# WiiIr.net
KiCad netlist of a schematic drawn in EAGLE
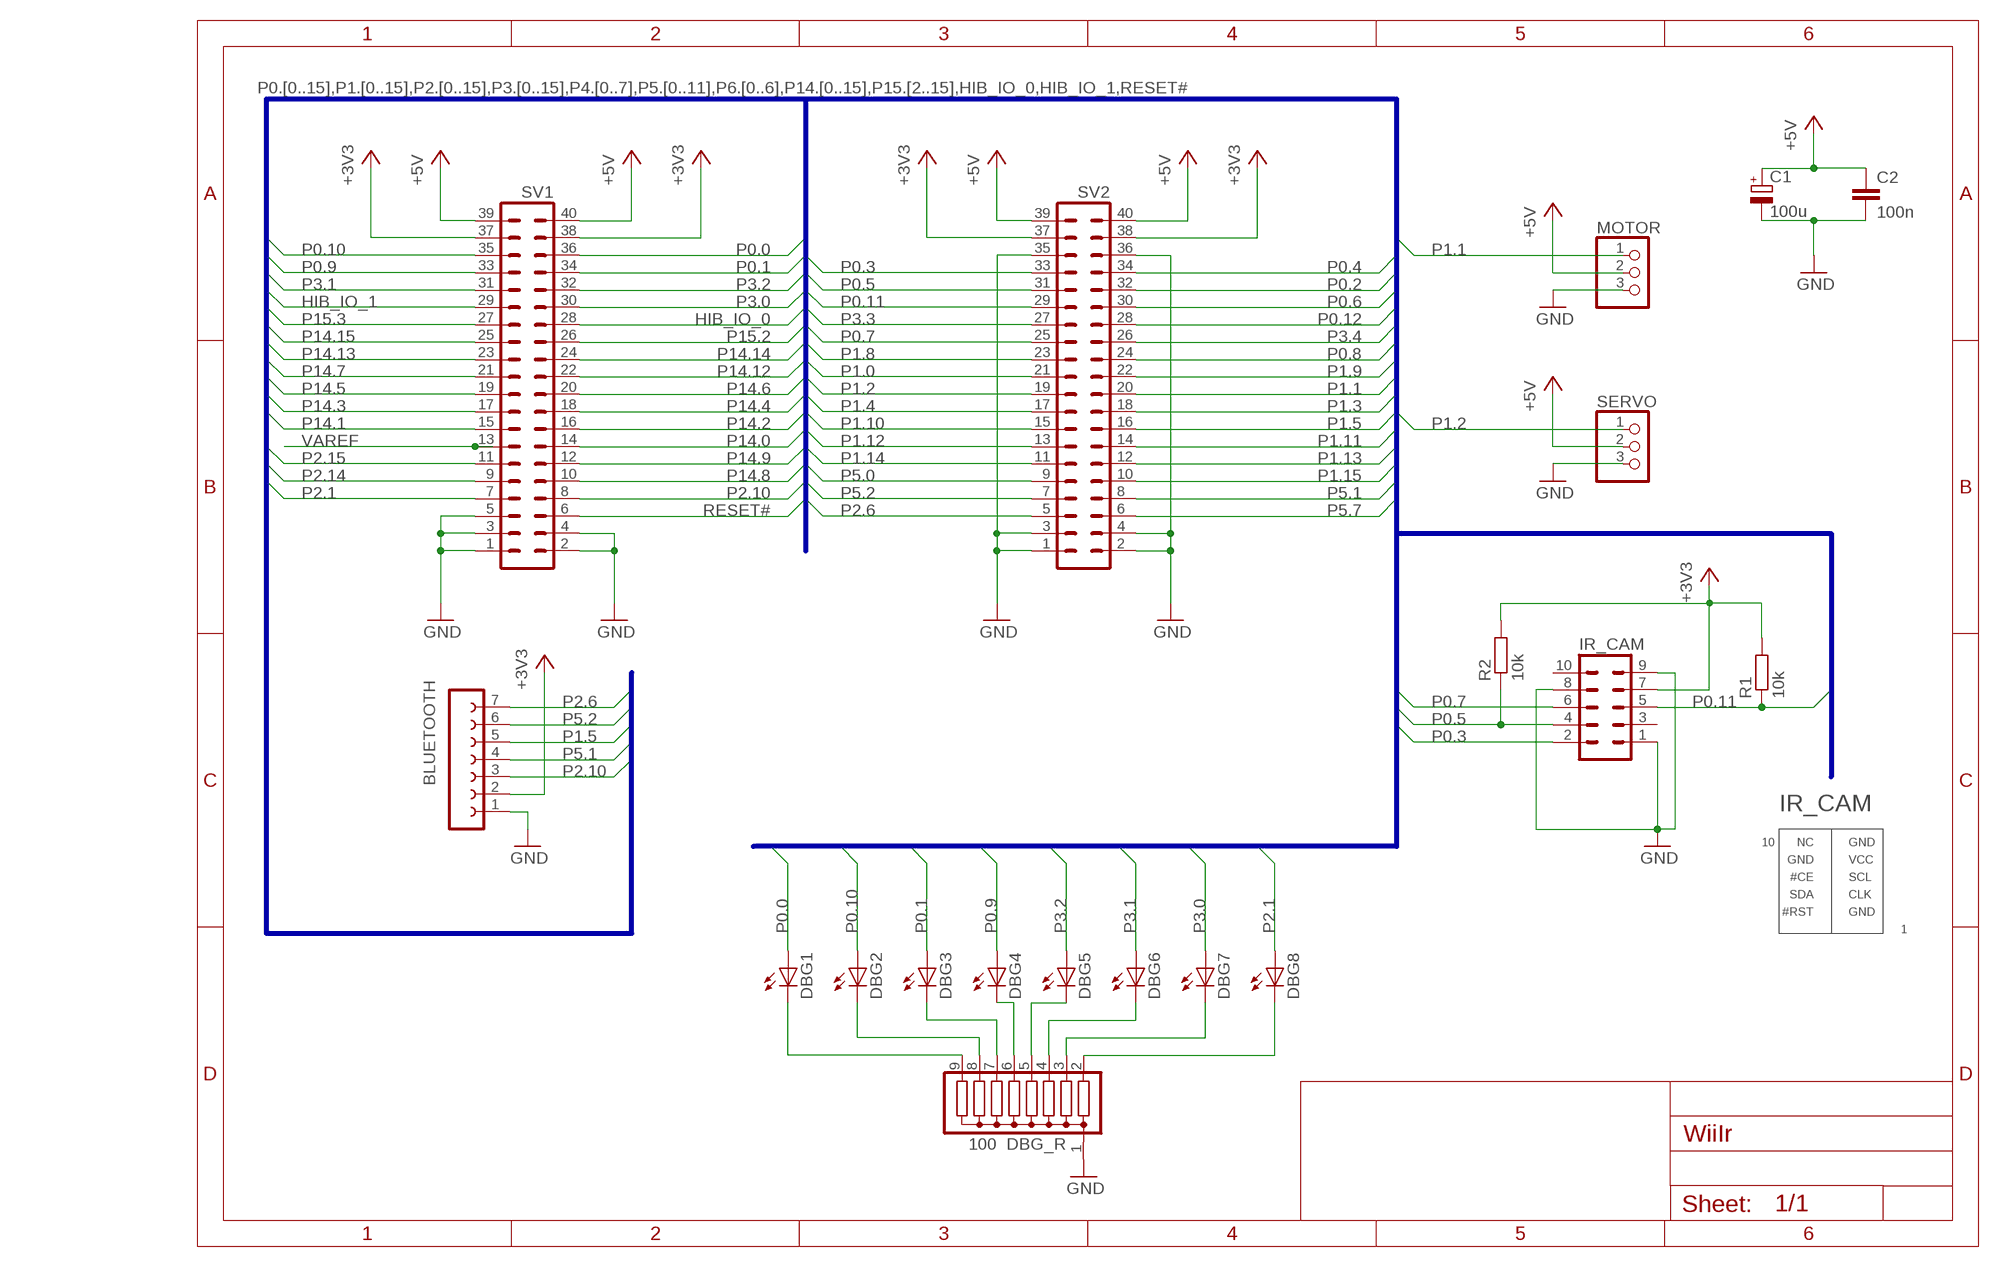
[diagram p0: schematic, sheet 1]

(export (version "E")
  (design (tool "Eeschema 10.0.6"))
  (components
    (comp (ref "BLUETOOTH")
      (value "FE07-1")
      (footprint "eagle-import:FE07")
      (libsource (lib "eagle-import") (part "FE07-1"))
    )
    (comp (ref "C1")
      (value "100u")
      (footprint "eagle-import:E2,5-7")
      (libsource (lib "eagle-import") (part "CPOL-EUE2.5-7"))
    )
    (comp (ref "C2")
      (value "100n")
      (footprint "eagle-import:C025-025X050")
      (libsource (lib "eagle-import") (part "C-EU025-025X050"))
    )
    (comp (ref "DBG1")
      (value "LEDSQR2X5")
      (footprint "eagle-import:LED2X5")
      (libsource (lib "eagle-import") (part "LEDSQR2X5"))
    )
    (comp (ref "DBG2")
      (value "LEDSQR2X5")
      (footprint "eagle-import:LED2X5")
      (libsource (lib "eagle-import") (part "LEDSQR2X5"))
    )
    (comp (ref "DBG3")
      (value "LEDSQR2X5")
      (footprint "eagle-import:LED2X5")
      (libsource (lib "eagle-import") (part "LEDSQR2X5"))
    )
    (comp (ref "DBG4")
      (value "LEDSQR2X5")
      (footprint "eagle-import:LED2X5")
      (libsource (lib "eagle-import") (part "LEDSQR2X5"))
    )
    (comp (ref "DBG5")
      (value "LEDSQR2X5")
      (footprint "eagle-import:LED2X5")
      (libsource (lib "eagle-import") (part "LEDSQR2X5"))
    )
    (comp (ref "DBG6")
      (value "LEDSQR2X5")
      (footprint "eagle-import:LED2X5")
      (libsource (lib "eagle-import") (part "LEDSQR2X5"))
    )
    (comp (ref "DBG7")
      (value "LEDSQR2X5")
      (footprint "eagle-import:LED2X5")
      (libsource (lib "eagle-import") (part "LEDSQR2X5"))
    )
    (comp (ref "DBG8")
      (value "LEDSQR2X5")
      (footprint "eagle-import:LED2X5")
      (libsource (lib "eagle-import") (part "LEDSQR2X5"))
    )
    (comp (ref "DBG_R")
      (value "100")
      (footprint "eagle-import:SIL9")
      (libsource (lib "eagle-import") (part "G08R"))
    )
    (comp (ref "IR_CAM")
      (value "ML10")
      (footprint "eagle-import:ML10")
      (libsource (lib "eagle-import") (part "ML10"))
    )
    (comp (ref "MOTOR")
      (value "PINHD-1X3/90")
      (footprint "eagle-import:1X03_90")
      (libsource (lib "eagle-import") (part "PINHD-1X3/90"))
    )
    (comp (ref "R1")
      (value "10k")
      (footprint "eagle-import:0207_12")
      (libsource (lib "eagle-import") (part "R-EU_0207/12"))
    )
    (comp (ref "R2")
      (value "10k")
      (footprint "eagle-import:0207_10")
      (libsource (lib "eagle-import") (part "R-EU_0207/10"))
    )
    (comp (ref "SERVO")
      (value "PINHD-1X3/90")
      (footprint "eagle-import:1X03_90")
      (libsource (lib "eagle-import") (part "PINHD-1X3/90"))
    )
    (comp (ref "SV1")
      (value "MA20-2")
      (footprint "eagle-import:MA20-2")
      (libsource (lib "eagle-import") (part "MA20-2"))
    )
    (comp (ref "SV2")
      (value "MA20-2")
      (footprint "eagle-import:MA20-2")
      (libsource (lib "eagle-import") (part "MA20-2"))
    )
  )
  (nets
    (net (code "1") (name "+3V3") (class "Default")
      (node (ref "BLUETOOTH") (pin "2") (pinfunction "2_2") (pintype "passive"))
      (node (ref "IR_CAM") (pin "7") (pinfunction "7_7") (pintype "passive"))
      (node (ref "R1") (pin "2") (pinfunction "2_2") (pintype "passive"))
      (node (ref "R2") (pin "2") (pinfunction "2_2") (pintype "passive"))
      (node (ref "SV1") (pin "37") (pinfunction "37_37") (pintype "passive"))
      (node (ref "SV1") (pin "38") (pinfunction "38_38") (pintype "passive"))
      (node (ref "SV2") (pin "37") (pinfunction "37_37") (pintype "passive"))
      (node (ref "SV2") (pin "38") (pinfunction "38_38") (pintype "passive"))
    )
    (net (code "2") (name "+5V") (class "Default")
      (node (ref "C1") (pin "+") (pinfunction "+_+") (pintype "passive"))
      (node (ref "C2") (pin "1") (pinfunction "1_1") (pintype "passive"))
      (node (ref "MOTOR") (pin "2") (pinfunction "2_2") (pintype "passive"))
      (node (ref "SERVO") (pin "2") (pinfunction "2_2") (pintype "passive"))
      (node (ref "SV1") (pin "39") (pinfunction "39_39") (pintype "passive"))
      (node (ref "SV1") (pin "40") (pinfunction "40_40") (pintype "passive"))
      (node (ref "SV2") (pin "39") (pinfunction "39_39") (pintype "passive"))
      (node (ref "SV2") (pin "40") (pinfunction "40_40") (pintype "passive"))
    )
    (net (code "3") (name "/HIB_IO_0") (class "Default")
      (node (ref "SV1") (pin "28") (pinfunction "28_28") (pintype "passive"))
    )
    (net (code "4") (name "/HIB_IO_1") (class "Default")
      (node (ref "SV1") (pin "29") (pinfunction "29_29") (pintype "passive"))
    )
    (net (code "5") (name "/P0.0") (class "Default")
      (node (ref "DBG1") (pin "A") (pinfunction "A_A") (pintype "passive"))
      (node (ref "SV1") (pin "36") (pinfunction "36_36") (pintype "passive"))
    )
    (net (code "6") (name "/P0.1") (class "Default")
      (node (ref "DBG3") (pin "A") (pinfunction "A_A") (pintype "passive"))
      (node (ref "SV1") (pin "34") (pinfunction "34_34") (pintype "passive"))
    )
    (net (code "7") (name "/P0.2") (class "Default")
      (node (ref "SV2") (pin "32") (pinfunction "32_32") (pintype "passive"))
    )
    (net (code "8") (name "/P0.3") (class "Default")
      (node (ref "IR_CAM") (pin "2") (pinfunction "2_2") (pintype "passive"))
      (node (ref "SV2") (pin "33") (pinfunction "33_33") (pintype "passive"))
    )
    (net (code "9") (name "/P0.4") (class "Default")
      (node (ref "SV2") (pin "34") (pinfunction "34_34") (pintype "passive"))
    )
    (net (code "10") (name "/P0.5") (class "Default")
      (node (ref "IR_CAM") (pin "4") (pinfunction "4_4") (pintype "passive"))
      (node (ref "R2") (pin "1") (pinfunction "1_1") (pintype "passive"))
      (node (ref "SV2") (pin "31") (pinfunction "31_31") (pintype "passive"))
    )
    (net (code "11") (name "/P0.6") (class "Default")
      (node (ref "SV2") (pin "30") (pinfunction "30_30") (pintype "passive"))
    )
    (net (code "12") (name "/P0.7") (class "Default")
      (node (ref "IR_CAM") (pin "6") (pinfunction "6_6") (pintype "passive"))
      (node (ref "SV2") (pin "25") (pinfunction "25_25") (pintype "passive"))
    )
    (net (code "13") (name "/P0.8") (class "Default")
      (node (ref "SV2") (pin "24") (pinfunction "24_24") (pintype "passive"))
    )
    (net (code "14") (name "/P0.9") (class "Default")
      (node (ref "DBG4") (pin "A") (pinfunction "A_A") (pintype "passive"))
      (node (ref "SV1") (pin "33") (pinfunction "33_33") (pintype "passive"))
    )
    (net (code "15") (name "/P0.10") (class "Default")
      (node (ref "DBG2") (pin "A") (pinfunction "A_A") (pintype "passive"))
      (node (ref "SV1") (pin "35") (pinfunction "35_35") (pintype "passive"))
    )
    (net (code "16") (name "/P0.11") (class "Default")
      (node (ref "IR_CAM") (pin "5") (pinfunction "5_5") (pintype "passive"))
      (node (ref "R1") (pin "1") (pinfunction "1_1") (pintype "passive"))
      (node (ref "SV2") (pin "29") (pinfunction "29_29") (pintype "passive"))
    )
    (net (code "17") (name "/P0.12") (class "Default")
      (node (ref "SV2") (pin "28") (pinfunction "28_28") (pintype "passive"))
    )
    (net (code "18") (name "/P1.0") (class "Default")
      (node (ref "SV2") (pin "21") (pinfunction "21_21") (pintype "passive"))
    )
    (net (code "19") (name "/P1.1") (class "Default")
      (node (ref "MOTOR") (pin "1") (pinfunction "1_1") (pintype "passive"))
      (node (ref "SV2") (pin "20") (pinfunction "20_20") (pintype "passive"))
    )
    (net (code "20") (name "/P1.2") (class "Default")
      (node (ref "SERVO") (pin "1") (pinfunction "1_1") (pintype "passive"))
      (node (ref "SV2") (pin "19") (pinfunction "19_19") (pintype "passive"))
    )
    (net (code "21") (name "/P1.3") (class "Default")
      (node (ref "SV2") (pin "18") (pinfunction "18_18") (pintype "passive"))
    )
    (net (code "22") (name "/P1.4") (class "Default")
      (node (ref "SV2") (pin "17") (pinfunction "17_17") (pintype "passive"))
    )
    (net (code "23") (name "/P1.5") (class "Default")
      (node (ref "BLUETOOTH") (pin "5") (pinfunction "5_5") (pintype "passive"))
      (node (ref "SV2") (pin "16") (pinfunction "16_16") (pintype "passive"))
    )
    (net (code "24") (name "/P1.8") (class "Default")
      (node (ref "SV2") (pin "23") (pinfunction "23_23") (pintype "passive"))
    )
    (net (code "25") (name "/P1.9") (class "Default")
      (node (ref "SV2") (pin "22") (pinfunction "22_22") (pintype "passive"))
    )
    (net (code "26") (name "/P1.10") (class "Default")
      (node (ref "SV2") (pin "15") (pinfunction "15_15") (pintype "passive"))
    )
    (net (code "27") (name "/P1.11") (class "Default")
      (node (ref "SV2") (pin "14") (pinfunction "14_14") (pintype "passive"))
    )
    (net (code "28") (name "/P1.12") (class "Default")
      (node (ref "SV2") (pin "13") (pinfunction "13_13") (pintype "passive"))
    )
    (net (code "29") (name "/P1.13") (class "Default")
      (node (ref "SV2") (pin "12") (pinfunction "12_12") (pintype "passive"))
    )
    (net (code "30") (name "/P1.14") (class "Default")
      (node (ref "SV2") (pin "11") (pinfunction "11_11") (pintype "passive"))
    )
    (net (code "31") (name "/P1.15") (class "Default")
      (node (ref "SV2") (pin "10") (pinfunction "10_10") (pintype "passive"))
    )
    (net (code "32") (name "/P2.1") (class "Default")
      (node (ref "DBG8") (pin "A") (pinfunction "A_A") (pintype "passive"))
      (node (ref "SV1") (pin "7") (pinfunction "7_7") (pintype "passive"))
    )
    (net (code "33") (name "/P2.6") (class "Default")
      (node (ref "BLUETOOTH") (pin "7") (pinfunction "7_7") (pintype "passive"))
      (node (ref "SV2") (pin "5") (pinfunction "5_5") (pintype "passive"))
    )
    (net (code "34") (name "/P2.10") (class "Default")
      (node (ref "BLUETOOTH") (pin "3") (pinfunction "3_3") (pintype "passive"))
      (node (ref "SV1") (pin "8") (pinfunction "8_8") (pintype "passive"))
    )
    (net (code "35") (name "/P2.14") (class "Default")
      (node (ref "SV1") (pin "9") (pinfunction "9_9") (pintype "passive"))
    )
    (net (code "36") (name "/P2.15") (class "Default")
      (node (ref "SV1") (pin "11") (pinfunction "11_11") (pintype "passive"))
    )
    (net (code "37") (name "/P3.0") (class "Default")
      (node (ref "DBG7") (pin "A") (pinfunction "A_A") (pintype "passive"))
      (node (ref "SV1") (pin "30") (pinfunction "30_30") (pintype "passive"))
    )
    (net (code "38") (name "/P3.1") (class "Default")
      (node (ref "DBG6") (pin "A") (pinfunction "A_A") (pintype "passive"))
      (node (ref "SV1") (pin "31") (pinfunction "31_31") (pintype "passive"))
    )
    (net (code "39") (name "/P3.2") (class "Default")
      (node (ref "DBG5") (pin "A") (pinfunction "A_A") (pintype "passive"))
      (node (ref "SV1") (pin "32") (pinfunction "32_32") (pintype "passive"))
    )
    (net (code "40") (name "/P3.3") (class "Default")
      (node (ref "SV2") (pin "27") (pinfunction "27_27") (pintype "passive"))
    )
    (net (code "41") (name "/P3.4") (class "Default")
      (node (ref "SV2") (pin "26") (pinfunction "26_26") (pintype "passive"))
    )
    (net (code "42") (name "/P5.0") (class "Default")
      (node (ref "SV2") (pin "9") (pinfunction "9_9") (pintype "passive"))
    )
    (net (code "43") (name "/P5.1") (class "Default")
      (node (ref "BLUETOOTH") (pin "4") (pinfunction "4_4") (pintype "passive"))
      (node (ref "SV2") (pin "8") (pinfunction "8_8") (pintype "passive"))
    )
    (net (code "44") (name "/P5.2") (class "Default")
      (node (ref "BLUETOOTH") (pin "6") (pinfunction "6_6") (pintype "passive"))
      (node (ref "SV2") (pin "7") (pinfunction "7_7") (pintype "passive"))
    )
    (net (code "45") (name "/P5.7") (class "Default")
      (node (ref "SV2") (pin "6") (pinfunction "6_6") (pintype "passive"))
    )
    (net (code "46") (name "/P14.0") (class "Default")
      (node (ref "SV1") (pin "14") (pinfunction "14_14") (pintype "passive"))
    )
    (net (code "47") (name "/P14.1") (class "Default")
      (node (ref "SV1") (pin "15") (pinfunction "15_15") (pintype "passive"))
    )
    (net (code "48") (name "/P14.2") (class "Default")
      (node (ref "SV1") (pin "16") (pinfunction "16_16") (pintype "passive"))
    )
    (net (code "49") (name "/P14.3") (class "Default")
      (node (ref "SV1") (pin "17") (pinfunction "17_17") (pintype "passive"))
    )
    (net (code "50") (name "/P14.4") (class "Default")
      (node (ref "SV1") (pin "18") (pinfunction "18_18") (pintype "passive"))
    )
    (net (code "51") (name "/P14.5") (class "Default")
      (node (ref "SV1") (pin "19") (pinfunction "19_19") (pintype "passive"))
    )
    (net (code "52") (name "/P14.6") (class "Default")
      (node (ref "SV1") (pin "20") (pinfunction "20_20") (pintype "passive"))
    )
    (net (code "53") (name "/P14.7") (class "Default")
      (node (ref "SV1") (pin "21") (pinfunction "21_21") (pintype "passive"))
    )
    (net (code "54") (name "/P14.8") (class "Default")
      (node (ref "SV1") (pin "10") (pinfunction "10_10") (pintype "passive"))
    )
    (net (code "55") (name "/P14.9") (class "Default")
      (node (ref "SV1") (pin "12") (pinfunction "12_12") (pintype "passive"))
    )
    (net (code "56") (name "/P14.12") (class "Default")
      (node (ref "SV1") (pin "22") (pinfunction "22_22") (pintype "passive"))
    )
    (net (code "57") (name "/P14.13") (class "Default")
      (node (ref "SV1") (pin "23") (pinfunction "23_23") (pintype "passive"))
    )
    (net (code "58") (name "/P14.14") (class "Default")
      (node (ref "SV1") (pin "24") (pinfunction "24_24") (pintype "passive"))
    )
    (net (code "59") (name "/P14.15") (class "Default")
      (node (ref "SV1") (pin "25") (pinfunction "25_25") (pintype "passive"))
    )
    (net (code "60") (name "/P15.2") (class "Default")
      (node (ref "SV1") (pin "26") (pinfunction "26_26") (pintype "passive"))
    )
    (net (code "61") (name "/P15.3") (class "Default")
      (node (ref "SV1") (pin "27") (pinfunction "27_27") (pintype "passive"))
    )
    (net (code "62") (name "/RESET#") (class "Default")
      (node (ref "SV1") (pin "6") (pinfunction "6_6") (pintype "passive"))
    )
    (net (code "63") (name "/VAREF") (class "Default")
      (node (ref "SV1") (pin "13") (pinfunction "13_13") (pintype "passive"))
    )
    (net (code "65") (name "GND") (class "Default")
      (node (ref "BLUETOOTH") (pin "1") (pinfunction "1_1") (pintype "passive"))
      (node (ref "C1") (pin "-") (pinfunction "-_-") (pintype "passive"))
      (node (ref "C2") (pin "2") (pinfunction "2_2") (pintype "passive"))
      (node (ref "DBG_R") (pin "1") (pinfunction "1_1") (pintype "passive"))
      (node (ref "IR_CAM") (pin "1") (pinfunction "1_1") (pintype "passive"))
      (node (ref "IR_CAM") (pin "8") (pinfunction "8_8") (pintype "passive"))
      (node (ref "IR_CAM") (pin "9") (pinfunction "9_9") (pintype "passive"))
      (node (ref "MOTOR") (pin "3") (pinfunction "3_3") (pintype "passive"))
      (node (ref "SERVO") (pin "3") (pinfunction "3_3") (pintype "passive"))
      (node (ref "SV1") (pin "1") (pinfunction "1_1") (pintype "passive"))
      (node (ref "SV1") (pin "2") (pinfunction "2_2") (pintype "passive"))
      (node (ref "SV1") (pin "3") (pinfunction "3_3") (pintype "passive"))
      (node (ref "SV1") (pin "4") (pinfunction "4_4") (pintype "passive"))
      (node (ref "SV1") (pin "5") (pinfunction "5_5") (pintype "passive"))
      (node (ref "SV2") (pin "1") (pinfunction "1_1") (pintype "passive"))
      (node (ref "SV2") (pin "2") (pinfunction "2_2") (pintype "passive"))
      (node (ref "SV2") (pin "3") (pinfunction "3_3") (pintype "passive"))
      (node (ref "SV2") (pin "35") (pinfunction "35_35") (pintype "passive"))
      (node (ref "SV2") (pin "36") (pinfunction "36_36") (pintype "passive"))
      (node (ref "SV2") (pin "4") (pinfunction "4_4") (pintype "passive"))
    )
    (net (code "66") (name "Net-(DBG1-C)") (class "Default")
      (node (ref "DBG1") (pin "K") (pinfunction "C_K") (pintype "passive"))
      (node (ref "DBG_R") (pin "9") (pinfunction "9_9") (pintype "passive"))
    )
    (net (code "67") (name "Net-(DBG2-C)") (class "Default")
      (node (ref "DBG2") (pin "K") (pinfunction "C_K") (pintype "passive"))
      (node (ref "DBG_R") (pin "8") (pinfunction "8_8") (pintype "passive"))
    )
    (net (code "68") (name "Net-(DBG3-C)") (class "Default")
      (node (ref "DBG3") (pin "K") (pinfunction "C_K") (pintype "passive"))
      (node (ref "DBG_R") (pin "7") (pinfunction "7_7") (pintype "passive"))
    )
    (net (code "69") (name "Net-(DBG4-C)") (class "Default")
      (node (ref "DBG4") (pin "K") (pinfunction "C_K") (pintype "passive"))
      (node (ref "DBG_R") (pin "6") (pinfunction "6_6") (pintype "passive"))
    )
    (net (code "70") (name "Net-(DBG5-C)") (class "Default")
      (node (ref "DBG5") (pin "K") (pinfunction "C_K") (pintype "passive"))
      (node (ref "DBG_R") (pin "5") (pinfunction "5_5") (pintype "passive"))
    )
    (net (code "71") (name "Net-(DBG6-C)") (class "Default")
      (node (ref "DBG6") (pin "K") (pinfunction "C_K") (pintype "passive"))
      (node (ref "DBG_R") (pin "4") (pinfunction "4_4") (pintype "passive"))
    )
    (net (code "72") (name "Net-(DBG7-C)") (class "Default")
      (node (ref "DBG7") (pin "K") (pinfunction "C_K") (pintype "passive"))
      (node (ref "DBG_R") (pin "3") (pinfunction "3_3") (pintype "passive"))
    )
    (net (code "73") (name "Net-(DBG8-C)") (class "Default")
      (node (ref "DBG8") (pin "K") (pinfunction "C_K") (pintype "passive"))
      (node (ref "DBG_R") (pin "2") (pinfunction "2_2") (pintype "passive"))
    )
    (net (code "74") (name "unconnected-(IR_CAM-Pad3)") (class "Default")
      (node (ref "IR_CAM") (pin "3") (pinfunction "3_3") (pintype "passive"))
    )
    (net (code "75") (name "unconnected-(IR_CAM-Pad10)") (class "Default")
      (node (ref "IR_CAM") (pin "10") (pinfunction "10_10") (pintype "passive"))
    )
  )
)
